# Clock_Schematic_v_4.net
KiCad netlist of a schematic drawn in EAGLE
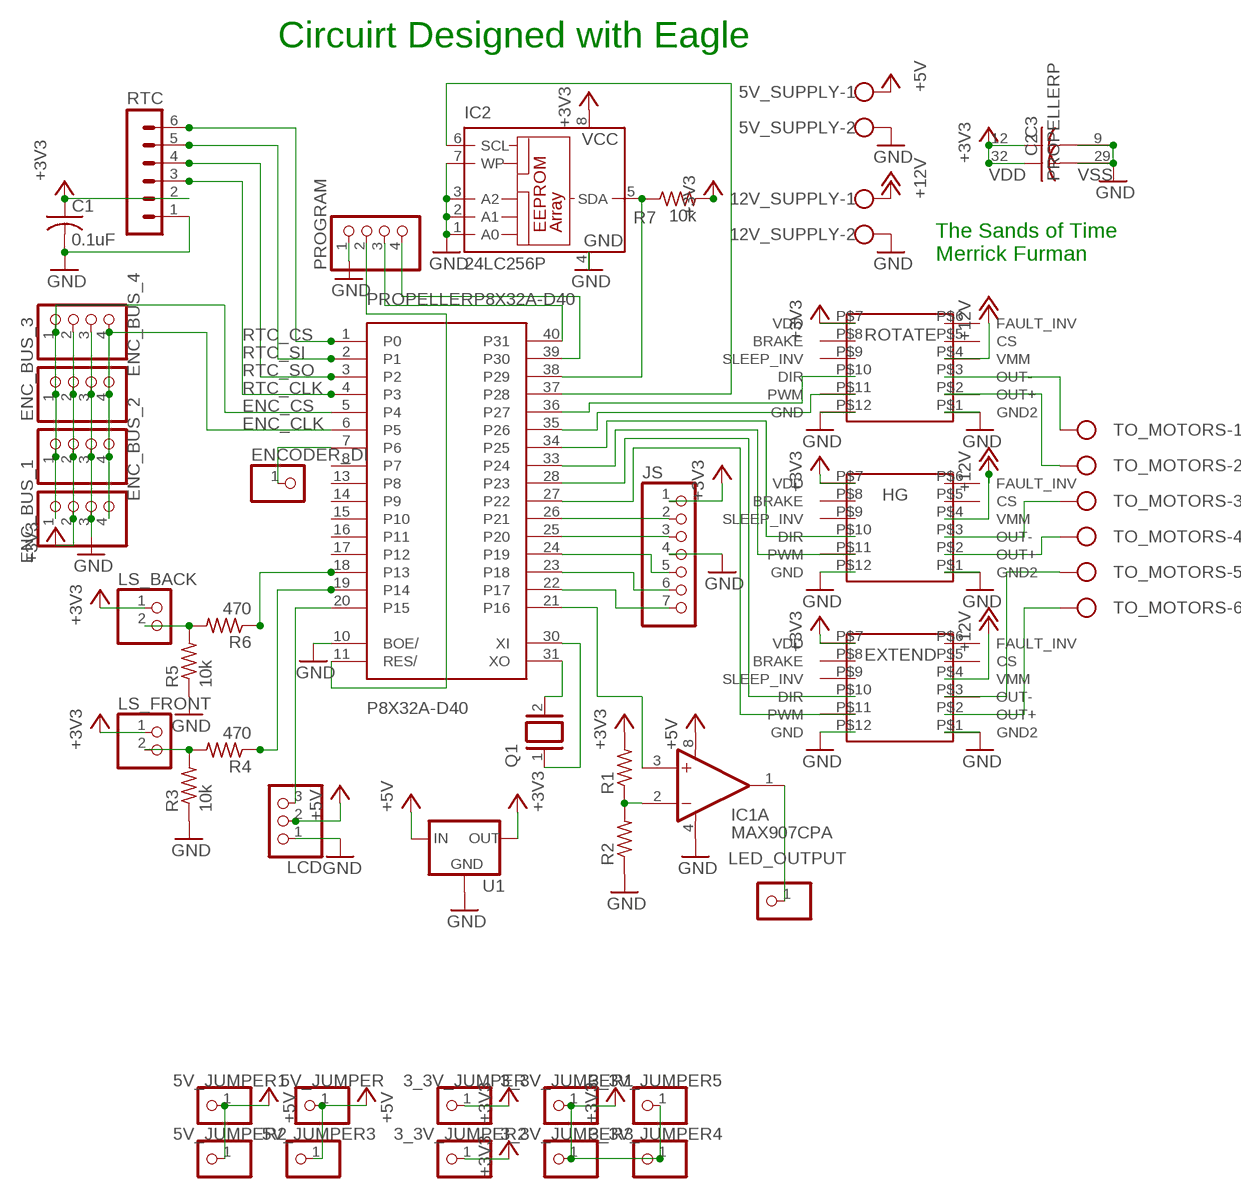
[diagram p0: schematic, sheet 1]

(export (version "E")
  (design (tool "Eeschema 10.0.6"))
  (components
    (comp (ref "3_3V_JUMPER")
      (value "PINHD-1X1")
      (footprint "eagle-import:1X01")
      (libsource (lib "eagle-import") (part "PINHD-1X1"))
    )
    (comp (ref "3_3V_JUMPER1")
      (value "PINHD-1X1")
      (footprint "eagle-import:1X01")
      (libsource (lib "eagle-import") (part "PINHD-1X1"))
    )
    (comp (ref "3_3V_JUMPER2")
      (value "PINHD-1X1")
      (footprint "eagle-import:1X01")
      (libsource (lib "eagle-import") (part "PINHD-1X1"))
    )
    (comp (ref "3_3V_JUMPER3")
      (value "PINHD-1X1")
      (footprint "eagle-import:1X01")
      (libsource (lib "eagle-import") (part "PINHD-1X1"))
    )
    (comp (ref "3_3V_JUMPER4")
      (value "PINHD-1X1")
      (footprint "eagle-import:1X01")
      (libsource (lib "eagle-import") (part "PINHD-1X1"))
    )
    (comp (ref "3_3V_JUMPER5")
      (value "PINHD-1X1")
      (footprint "eagle-import:1X01")
      (libsource (lib "eagle-import") (part "PINHD-1X1"))
    )
    (comp (ref "5V_JUMPER")
      (value "PINHD-1X1")
      (footprint "eagle-import:1X01")
      (libsource (lib "eagle-import") (part "PINHD-1X1"))
    )
    (comp (ref "5V_JUMPER1")
      (value "PINHD-1X1")
      (footprint "eagle-import:1X01")
      (libsource (lib "eagle-import") (part "PINHD-1X1"))
    )
    (comp (ref "5V_JUMPER2")
      (value "PINHD-1X1")
      (footprint "eagle-import:1X01")
      (libsource (lib "eagle-import") (part "PINHD-1X1"))
    )
    (comp (ref "5V_JUMPER3")
      (value "PINHD-1X1")
      (footprint "eagle-import:1X01")
      (libsource (lib "eagle-import") (part "PINHD-1X1"))
    )
    (comp (ref "5V_SUPPLY")
      (value "W237-102")
      (footprint "eagle-import:W237-102")
      (fields (field (name "MPN") "237-102"))
      (libsource (lib "eagle-import") (part "W237-102"))
    )
    (comp (ref "12V_SUPPLY")
      (value "W237-102")
      (footprint "eagle-import:W237-102")
      (fields (field (name "MPN") "237-102"))
      (libsource (lib "eagle-import") (part "W237-102"))
    )
    (comp (ref "C1")
      (value "0.1uF")
      (footprint "eagle-import:C050-025X075")
      (libsource (lib "eagle-import") (part "C-US050-025X075"))
    )
    (comp (ref "C2")
      (value "C-US050-025X075")
      (footprint "eagle-import:C050-025X075")
      (libsource (lib "eagle-import") (part "C-US050-025X075"))
    )
    (comp (ref "C3")
      (value "C-US050-025X075")
      (footprint "eagle-import:C050-025X075")
      (libsource (lib "eagle-import") (part "C-US050-025X075"))
    )
    (comp (ref "ENCODER_DI")
      (value "PINHD-1X1")
      (footprint "eagle-import:1X01")
      (libsource (lib "eagle-import") (part "PINHD-1X1"))
    )
    (comp (ref "ENC_BUS_1")
      (value "PINHD-1X4")
      (footprint "eagle-import:1X04")
      (libsource (lib "eagle-import") (part "PINHD-1X4"))
    )
    (comp (ref "ENC_BUS_2")
      (value "PINHD-1X4")
      (footprint "eagle-import:1X04")
      (libsource (lib "eagle-import") (part "PINHD-1X4"))
    )
    (comp (ref "ENC_BUS_3")
      (value "PINHD-1X4")
      (footprint "eagle-import:1X04")
      (libsource (lib "eagle-import") (part "PINHD-1X4"))
    )
    (comp (ref "ENC_BUS_4")
      (value "PINHD-1X4")
      (footprint "eagle-import:1X04")
      (libsource (lib "eagle-import") (part "PINHD-1X4"))
    )
    (comp (ref "EXTEND")
      (value "DRV")
      (footprint "eagle-import:DRV")
      (libsource (lib "eagle-import") (part "DRV"))
    )
    (comp (ref "HG")
      (value "DRV")
      (footprint "eagle-import:DRV")
      (libsource (lib "eagle-import") (part "DRV"))
    )
    (comp (ref "IC1")
      (value "MAX907CPA")
      (footprint "eagle-import:DIL08")
      (fields (field (name "MF") "MAXIM"))
      (libsource (lib "eagle-import") (part "MAX907CPA"))
    )
    (comp (ref "IC2")
      (value "24LC256P")
      (footprint "eagle-import:DIL8")
      (fields (field (name "MF") "MICROCHIP") (field (name "MPN") "24LC256-E/P"))
      (libsource (lib "eagle-import") (part "24PLC256"))
    )
    (comp (ref "JS")
      (value "PINHD-1X7")
      (footprint "eagle-import:1X07")
      (libsource (lib "eagle-import") (part "PINHD-1X7"))
    )
    (comp (ref "LCD")
      (value "PINHD-1X3")
      (footprint "eagle-import:1X03")
      (libsource (lib "eagle-import") (part "PINHD-1X3"))
    )
    (comp (ref "LED_OUTPUT")
      (value "PINHD-1X1")
      (footprint "eagle-import:1X01")
      (libsource (lib "eagle-import") (part "PINHD-1X1"))
    )
    (comp (ref "LS_BACK")
      (value "PINHD-1X2")
      (footprint "eagle-import:1X02")
      (libsource (lib "eagle-import") (part "PINHD-1X2"))
    )
    (comp (ref "LS_FRONT")
      (value "PINHD-1X2")
      (footprint "eagle-import:1X02")
      (libsource (lib "eagle-import") (part "PINHD-1X2"))
    )
    (comp (ref "PROGRAM")
      (value "PINHD-1X4")
      (footprint "eagle-import:1X04")
      (libsource (lib "eagle-import") (part "PINHD-1X4"))
    )
    (comp (ref "PROPELLER")
      (value "P8X32A-D40")
      (footprint "eagle-import:P8X32A-D40")
      (libsource (lib "eagle-import") (part "P8X32A-D40"))
    )
    (comp (ref "Q1")
      (value "XTAL/S")
      (footprint "eagle-import:QS")
      (libsource (lib "eagle-import") (part "XTAL/S"))
    )
    (comp (ref "R1")
      (value "R-US_0207/10")
      (footprint "eagle-import:0207_10")
      (libsource (lib "eagle-import") (part "R-US_0207/10"))
    )
    (comp (ref "R2")
      (value "R-US_0207/10")
      (footprint "eagle-import:0207_10")
      (libsource (lib "eagle-import") (part "R-US_0207/10"))
    )
    (comp (ref "R3")
      (value "10k")
      (footprint "eagle-import:0207_10")
      (libsource (lib "eagle-import") (part "R-US_0207/10"))
    )
    (comp (ref "R4")
      (value "470")
      (footprint "eagle-import:0207_10")
      (libsource (lib "eagle-import") (part "R-US_0207/10"))
    )
    (comp (ref "R5")
      (value "10k")
      (footprint "eagle-import:0207_10")
      (libsource (lib "eagle-import") (part "R-US_0207/10"))
    )
    (comp (ref "R6")
      (value "470")
      (footprint "eagle-import:0207_10")
      (libsource (lib "eagle-import") (part "R-US_0207/10"))
    )
    (comp (ref "R7")
      (value "10k")
      (footprint "eagle-import:0207_10")
      (libsource (lib "eagle-import") (part "R-US_0207/10"))
    )
    (comp (ref "ROTATE")
      (value "DRV")
      (footprint "eagle-import:DRV")
      (libsource (lib "eagle-import") (part "DRV"))
    )
    (comp (ref "RTC")
      (value "MA06-1")
      (footprint "eagle-import:MA06-1")
      (libsource (lib "eagle-import") (part "MA06-1"))
    )
    (comp (ref "TO_MOTORS")
      (value "W237-6")
      (footprint "eagle-import:W237-6")
      (libsource (lib "eagle-import") (part "W237-6"))
    )
    (comp (ref "U1")
      (value "V_REG_78XXSIDE")
      (footprint "eagle-import:78XXL")
      (libsource (lib "eagle-import") (part "V_REG_78XXSIDE"))
    )
  )
  (nets
    (net (code "1") (name "+3V3") (class "Default")
      (node (ref "3_3V_JUMPER") (pin "1") (pinfunction "1_1") (pintype "passive"))
      (node (ref "3_3V_JUMPER1") (pin "1") (pinfunction "1_1") (pintype "passive"))
      (node (ref "3_3V_JUMPER2") (pin "1") (pinfunction "1_1") (pintype "passive"))
      (node (ref "3_3V_JUMPER3") (pin "1") (pinfunction "1_1") (pintype "passive"))
      (node (ref "3_3V_JUMPER4") (pin "1") (pinfunction "1_1") (pintype "passive"))
      (node (ref "3_3V_JUMPER5") (pin "1") (pinfunction "1_1") (pintype "passive"))
      (node (ref "C1") (pin "1") (pinfunction "1_1") (pintype "passive"))
      (node (ref "C2") (pin "1") (pinfunction "1_1") (pintype "passive"))
      (node (ref "C3") (pin "1") (pinfunction "1_1") (pintype "passive"))
      (node (ref "ENC_BUS_1") (pin "2") (pinfunction "2_2") (pintype "passive"))
      (node (ref "ENC_BUS_2") (pin "2") (pinfunction "2_2") (pintype "passive"))
      (node (ref "ENC_BUS_3") (pin "2") (pinfunction "2_2") (pintype "passive"))
      (node (ref "ENC_BUS_4") (pin "2") (pinfunction "2_2") (pintype "passive"))
      (node (ref "EXTEND") (pin "P$7") (pinfunction "VDD_P$7") (pintype "bidirectional"))
      (node (ref "HG") (pin "P$7") (pinfunction "VDD_P$7") (pintype "bidirectional"))
      (node (ref "IC2") (pin "8") (pinfunction "VCC_8") (pintype "power_in"))
      (node (ref "JS") (pin "1") (pinfunction "1_1") (pintype "passive"))
      (node (ref "LS_BACK") (pin "1") (pinfunction "1_1") (pintype "passive"))
      (node (ref "LS_FRONT") (pin "1") (pinfunction "1_1") (pintype "passive"))
      (node (ref "PROPELLER") (pin "12") (pinfunction "VDD_12") (pintype "power_in"))
      (node (ref "PROPELLER") (pin "32") (pinfunction "VDD_32") (pintype "power_in"))
      (node (ref "R1") (pin "2") (pinfunction "2_2") (pintype "passive"))
      (node (ref "R7") (pin "2") (pinfunction "2_2") (pintype "passive"))
      (node (ref "ROTATE") (pin "P$7") (pinfunction "VDD_P$7") (pintype "bidirectional"))
      (node (ref "RTC") (pin "2") (pinfunction "2_2") (pintype "passive"))
      (node (ref "U1") (pin "OUT") (pinfunction "OUT_OUT") (pintype "passive"))
    )
    (net (code "2") (name "+5V") (class "Default")
      (node (ref "5V_JUMPER") (pin "1") (pinfunction "1_1") (pintype "passive"))
      (node (ref "5V_JUMPER1") (pin "1") (pinfunction "1_1") (pintype "passive"))
      (node (ref "5V_JUMPER2") (pin "1") (pinfunction "1_1") (pintype "passive"))
      (node (ref "5V_JUMPER3") (pin "1") (pinfunction "1_1") (pintype "passive"))
      (node (ref "5V_SUPPLY") (pin "1") (pinfunction "KL_1") (pintype "passive"))
      (node (ref "IC1") (pin "8") (pinfunction "V+_8") (pintype "power_in"))
      (node (ref "LCD") (pin "2") (pinfunction "2_2") (pintype "passive"))
      (node (ref "U1") (pin "IN") (pinfunction "IN_IN") (pintype "input"))
    )
    (net (code "3") (name "+12V") (class "Default")
      (node (ref "12V_SUPPLY") (pin "1") (pinfunction "KL_1") (pintype "passive"))
      (node (ref "EXTEND") (pin "P$4") (pinfunction "VMM_P$4") (pintype "bidirectional"))
      (node (ref "HG") (pin "P$4") (pinfunction "VMM_P$4") (pintype "bidirectional"))
      (node (ref "ROTATE") (pin "P$4") (pinfunction "VMM_P$4") (pintype "bidirectional"))
    )
    (net (code "4") (name "/ENC_CLK") (class "Default")
      (node (ref "ENC_BUS_1") (pin "4") (pinfunction "4_4") (pintype "passive"))
      (node (ref "ENC_BUS_2") (pin "4") (pinfunction "4_4") (pintype "passive"))
      (node (ref "ENC_BUS_3") (pin "4") (pinfunction "4_4") (pintype "passive"))
      (node (ref "ENC_BUS_4") (pin "4") (pinfunction "4_4") (pintype "passive"))
      (node (ref "PROPELLER") (pin "6") (pinfunction "P5_6") (pintype "bidirectional"))
    )
    (net (code "5") (name "/ENC_CS") (class "Default")
      (node (ref "ENC_BUS_1") (pin "1") (pinfunction "1_1") (pintype "passive"))
      (node (ref "ENC_BUS_2") (pin "1") (pinfunction "1_1") (pintype "passive"))
      (node (ref "ENC_BUS_3") (pin "1") (pinfunction "1_1") (pintype "passive"))
      (node (ref "ENC_BUS_4") (pin "1") (pinfunction "1_1") (pintype "passive"))
      (node (ref "PROPELLER") (pin "5") (pinfunction "P4_5") (pintype "bidirectional"))
    )
    (net (code "6") (name "/RTC_CLK") (class "Default")
      (node (ref "PROPELLER") (pin "4") (pinfunction "P3_4") (pintype "bidirectional"))
      (node (ref "RTC") (pin "3") (pinfunction "3_3") (pintype "passive"))
    )
    (net (code "7") (name "/RTC_CS") (class "Default")
      (node (ref "PROPELLER") (pin "1") (pinfunction "P0_1") (pintype "bidirectional"))
      (node (ref "RTC") (pin "6") (pinfunction "6_6") (pintype "passive"))
    )
    (net (code "8") (name "/RTC_SI") (class "Default")
      (node (ref "PROPELLER") (pin "2") (pinfunction "P1_2") (pintype "bidirectional"))
      (node (ref "RTC") (pin "5") (pinfunction "5_5") (pintype "passive"))
    )
    (net (code "9") (name "/RTC_SO") (class "Default")
      (node (ref "PROPELLER") (pin "3") (pinfunction "P2_3") (pintype "bidirectional"))
      (node (ref "RTC") (pin "4") (pinfunction "4_4") (pintype "passive"))
    )
    (net (code "10") (name "GND") (class "Default")
      (node (ref "12V_SUPPLY") (pin "2") (pinfunction "KL_2") (pintype "passive"))
      (node (ref "5V_SUPPLY") (pin "2") (pinfunction "KL_2") (pintype "passive"))
      (node (ref "C1") (pin "2") (pinfunction "2_2") (pintype "passive"))
      (node (ref "C2") (pin "2") (pinfunction "2_2") (pintype "passive"))
      (node (ref "C3") (pin "2") (pinfunction "2_2") (pintype "passive"))
      (node (ref "ENC_BUS_1") (pin "3") (pinfunction "3_3") (pintype "passive"))
      (node (ref "ENC_BUS_2") (pin "3") (pinfunction "3_3") (pintype "passive"))
      (node (ref "ENC_BUS_3") (pin "3") (pinfunction "3_3") (pintype "passive"))
      (node (ref "ENC_BUS_4") (pin "3") (pinfunction "3_3") (pintype "passive"))
      (node (ref "EXTEND") (pin "P$1") (pinfunction "GND2_P$1") (pintype "bidirectional"))
      (node (ref "EXTEND") (pin "P$12") (pinfunction "GND_P$12") (pintype "bidirectional"))
      (node (ref "HG") (pin "P$1") (pinfunction "GND2_P$1") (pintype "bidirectional"))
      (node (ref "HG") (pin "P$12") (pinfunction "GND_P$12") (pintype "bidirectional"))
      (node (ref "IC1") (pin "4") (pinfunction "V-_4") (pintype "power_in"))
      (node (ref "IC2") (pin "1") (pinfunction "A0_1") (pintype "input"))
      (node (ref "IC2") (pin "2") (pinfunction "A1_2") (pintype "input"))
      (node (ref "IC2") (pin "3") (pinfunction "A2_3") (pintype "input"))
      (node (ref "IC2") (pin "4") (pinfunction "GND_4") (pintype "power_in"))
      (node (ref "IC2") (pin "7") (pinfunction "WP_7") (pintype "input"))
      (node (ref "JS") (pin "4") (pinfunction "4_4") (pintype "passive"))
      (node (ref "LCD") (pin "1") (pinfunction "1_1") (pintype "passive"))
      (node (ref "PROGRAM") (pin "1") (pinfunction "1_1") (pintype "passive"))
      (node (ref "PROPELLER") (pin "10") (pinfunction "BOE/_10") (pintype "input"))
      (node (ref "PROPELLER") (pin "29") (pinfunction "VSS_29") (pintype "power_in"))
      (node (ref "PROPELLER") (pin "9") (pinfunction "VSS_9") (pintype "power_in"))
      (node (ref "R2") (pin "1") (pinfunction "1_1") (pintype "passive"))
      (node (ref "R3") (pin "1") (pinfunction "1_1") (pintype "passive"))
      (node (ref "R5") (pin "1") (pinfunction "1_1") (pintype "passive"))
      (node (ref "ROTATE") (pin "P$1") (pinfunction "GND2_P$1") (pintype "bidirectional"))
      (node (ref "ROTATE") (pin "P$12") (pinfunction "GND_P$12") (pintype "bidirectional"))
      (node (ref "RTC") (pin "1") (pinfunction "1_1") (pintype "passive"))
      (node (ref "U1") (pin "GND") (pinfunction "GND_GND") (pintype "input"))
    )
    (net (code "11") (name "Net-(EXTEND-DIR)") (class "Default")
      (node (ref "EXTEND") (pin "P$10") (pinfunction "DIR_P$10") (pintype "bidirectional"))
      (node (ref "PROPELLER") (pin "28") (pinfunction "P23_28") (pintype "bidirectional"))
    )
    (net (code "12") (name "Net-(EXTEND-OUT+)") (class "Default")
      (node (ref "EXTEND") (pin "P$2") (pinfunction "OUT+_P$2") (pintype "bidirectional"))
      (node (ref "TO_MOTORS") (pin "6") (pinfunction "KL_6") (pintype "passive"))
    )
    (net (code "13") (name "Net-(EXTEND-OUT-)") (class "Default")
      (node (ref "EXTEND") (pin "P$3") (pinfunction "OUT-_P$3") (pintype "bidirectional"))
      (node (ref "TO_MOTORS") (pin "5") (pinfunction "KL_5") (pintype "passive"))
    )
    (net (code "14") (name "Net-(EXTEND-PWM)") (class "Default")
      (node (ref "EXTEND") (pin "P$11") (pinfunction "PWM_P$11") (pintype "bidirectional"))
      (node (ref "PROPELLER") (pin "27") (pinfunction "P22_27") (pintype "bidirectional"))
    )
    (net (code "15") (name "Net-(HG-DIR)") (class "Default")
      (node (ref "HG") (pin "P$10") (pinfunction "DIR_P$10") (pintype "bidirectional"))
      (node (ref "PROPELLER") (pin "34") (pinfunction "P25_34") (pintype "bidirectional"))
    )
    (net (code "16") (name "Net-(HG-OUT+)") (class "Default")
      (node (ref "HG") (pin "P$2") (pinfunction "OUT+_P$2") (pintype "bidirectional"))
      (node (ref "TO_MOTORS") (pin "4") (pinfunction "KL_4") (pintype "passive"))
    )
    (net (code "17") (name "Net-(HG-OUT-)") (class "Default")
      (node (ref "HG") (pin "P$3") (pinfunction "OUT-_P$3") (pintype "bidirectional"))
      (node (ref "TO_MOTORS") (pin "3") (pinfunction "KL_3") (pintype "passive"))
    )
    (net (code "18") (name "Net-(HG-PWM)") (class "Default")
      (node (ref "HG") (pin "P$11") (pinfunction "PWM_P$11") (pintype "bidirectional"))
      (node (ref "PROPELLER") (pin "33") (pinfunction "P24_33") (pintype "bidirectional"))
    )
    (net (code "19") (name "Net-(IC1A-+IN)") (class "Default")
      (node (ref "IC1") (pin "3") (pinfunction "+IN_3") (pintype "input"))
      (node (ref "PROPELLER") (pin "21") (pinfunction "P16_21") (pintype "bidirectional"))
    )
    (net (code "20") (name "Net-(IC1A--IN)") (class "Default")
      (node (ref "IC1") (pin "2") (pinfunction "-IN_2") (pintype "input"))
      (node (ref "R1") (pin "1") (pinfunction "1_1") (pintype "passive"))
      (node (ref "R2") (pin "2") (pinfunction "2_2") (pintype "passive"))
    )
    (net (code "21") (name "Net-(IC1A-OUT)") (class "Default")
      (node (ref "IC1") (pin "1") (pinfunction "OUT_1") (pintype "output"))
      (node (ref "LED_OUTPUT") (pin "1") (pinfunction "1_1") (pintype "passive"))
    )
    (net (code "22") (name "Net-(IC2-SCL)") (class "Default")
      (node (ref "IC2") (pin "6") (pinfunction "SCL_6") (pintype "input"))
      (node (ref "PROPELLER") (pin "37") (pinfunction "P28_37") (pintype "bidirectional"))
    )
    (net (code "23") (name "Net-(IC2-SDA)") (class "Default")
      (node (ref "IC2") (pin "5") (pinfunction "SDA_5") (pintype "bidirectional"))
      (node (ref "PROPELLER") (pin "38") (pinfunction "P29_38") (pintype "bidirectional"))
      (node (ref "R7") (pin "1") (pinfunction "1_1") (pintype "passive"))
    )
    (net (code "24") (name "Net-(LS_BACK-Pad2)") (class "Default")
      (node (ref "LS_BACK") (pin "2") (pinfunction "2_2") (pintype "passive"))
      (node (ref "R5") (pin "2") (pinfunction "2_2") (pintype "passive"))
      (node (ref "R6") (pin "2") (pinfunction "2_2") (pintype "passive"))
    )
    (net (code "25") (name "Net-(LS_FRONT-Pad2)") (class "Default")
      (node (ref "LS_FRONT") (pin "2") (pinfunction "2_2") (pintype "passive"))
      (node (ref "R3") (pin "2") (pinfunction "2_2") (pintype "passive"))
      (node (ref "R4") (pin "2") (pinfunction "2_2") (pintype "passive"))
    )
    (net (code "26") (name "Net-(PROPELLERB-P6)") (class "Default")
      (node (ref "ENCODER_DI") (pin "1") (pinfunction "1_1") (pintype "passive"))
      (node (ref "PROPELLER") (pin "7") (pinfunction "P6_7") (pintype "bidirectional"))
    )
    (net (code "27") (name "Net-(PROPELLERB-P13)") (class "Default")
      (node (ref "PROPELLER") (pin "18") (pinfunction "P13_18") (pintype "bidirectional"))
      (node (ref "R6") (pin "1") (pinfunction "1_1") (pintype "passive"))
    )
    (net (code "28") (name "Net-(PROPELLERB-P14)") (class "Default")
      (node (ref "PROPELLER") (pin "19") (pinfunction "P14_19") (pintype "bidirectional"))
      (node (ref "R4") (pin "1") (pinfunction "1_1") (pintype "passive"))
    )
    (net (code "29") (name "Net-(PROPELLERB-P15)") (class "Default")
      (node (ref "LCD") (pin "3") (pinfunction "3_3") (pintype "passive"))
      (node (ref "PROPELLER") (pin "20") (pinfunction "P15_20") (pintype "bidirectional"))
    )
    (net (code "30") (name "Net-(PROPELLERB-P17)") (class "Default")
      (node (ref "JS") (pin "7") (pinfunction "7_7") (pintype "passive"))
      (node (ref "PROPELLER") (pin "22") (pinfunction "P17_22") (pintype "bidirectional"))
    )
    (net (code "31") (name "Net-(PROPELLERB-P18)") (class "Default")
      (node (ref "JS") (pin "6") (pinfunction "6_6") (pintype "passive"))
      (node (ref "PROPELLER") (pin "23") (pinfunction "P18_23") (pintype "bidirectional"))
    )
    (net (code "32") (name "Net-(PROPELLERB-P19)") (class "Default")
      (node (ref "JS") (pin "5") (pinfunction "5_5") (pintype "passive"))
      (node (ref "PROPELLER") (pin "24") (pinfunction "P19_24") (pintype "bidirectional"))
    )
    (net (code "33") (name "Net-(PROPELLERB-P20)") (class "Default")
      (node (ref "JS") (pin "3") (pinfunction "3_3") (pintype "passive"))
      (node (ref "PROPELLER") (pin "25") (pinfunction "P20_25") (pintype "bidirectional"))
    )
    (net (code "34") (name "Net-(PROPELLERB-P21)") (class "Default")
      (node (ref "JS") (pin "2") (pinfunction "2_2") (pintype "passive"))
      (node (ref "PROPELLER") (pin "26") (pinfunction "P21_26") (pintype "bidirectional"))
    )
    (net (code "35") (name "Net-(PROPELLERB-P26)") (class "Default")
      (node (ref "PROPELLER") (pin "35") (pinfunction "P26_35") (pintype "bidirectional"))
      (node (ref "ROTATE") (pin "P$11") (pinfunction "PWM_P$11") (pintype "bidirectional"))
    )
    (net (code "36") (name "Net-(PROPELLERB-P27)") (class "Default")
      (node (ref "PROPELLER") (pin "36") (pinfunction "P27_36") (pintype "bidirectional"))
      (node (ref "ROTATE") (pin "P$10") (pinfunction "DIR_P$10") (pintype "bidirectional"))
    )
    (net (code "37") (name "Net-(PROPELLERB-P30)") (class "Default")
      (node (ref "PROGRAM") (pin "4") (pinfunction "4_4") (pintype "passive"))
      (node (ref "PROPELLER") (pin "39") (pinfunction "P30_39") (pintype "bidirectional"))
    )
    (net (code "38") (name "Net-(PROPELLERB-P31)") (class "Default")
      (node (ref "PROGRAM") (pin "3") (pinfunction "3_3") (pintype "passive"))
      (node (ref "PROPELLER") (pin "40") (pinfunction "P31_40") (pintype "bidirectional"))
    )
    (net (code "39") (name "Net-(PROPELLERB-RES{slash})") (class "Default")
      (node (ref "PROGRAM") (pin "2") (pinfunction "2_2") (pintype "passive"))
      (node (ref "PROPELLER") (pin "11") (pinfunction "RES/_11") (pintype "bidirectional"))
    )
    (net (code "40") (name "Net-(PROPELLERB-XI)") (class "Default")
      (node (ref "PROPELLER") (pin "30") (pinfunction "XI_30") (pintype "input"))
      (node (ref "Q1") (pin "1") (pinfunction "1_1") (pintype "passive"))
    )
    (net (code "41") (name "Net-(PROPELLERB-XO)") (class "Default")
      (node (ref "PROPELLER") (pin "31") (pinfunction "XO_31") (pintype "output"))
      (node (ref "Q1") (pin "2") (pinfunction "2_2") (pintype "passive"))
    )
    (net (code "42") (name "Net-(ROTATE-OUT+)") (class "Default")
      (node (ref "ROTATE") (pin "P$2") (pinfunction "OUT+_P$2") (pintype "bidirectional"))
      (node (ref "TO_MOTORS") (pin "2") (pinfunction "KL_2") (pintype "passive"))
    )
    (net (code "43") (name "Net-(ROTATE-OUT-)") (class "Default")
      (node (ref "ROTATE") (pin "P$3") (pinfunction "OUT-_P$3") (pintype "bidirectional"))
      (node (ref "TO_MOTORS") (pin "1") (pinfunction "KL_1") (pintype "passive"))
    )
    (net (code "44") (name "unconnected-(EXTEND-BRAKE-PadP$8)") (class "Default")
      (node (ref "EXTEND") (pin "P$8") (pinfunction "BRAKE_P$8") (pintype "bidirectional"))
    )
    (net (code "45") (name "unconnected-(EXTEND-CS-PadP$5)") (class "Default")
      (node (ref "EXTEND") (pin "P$5") (pinfunction "CS_P$5") (pintype "bidirectional"))
    )
    (net (code "46") (name "unconnected-(EXTEND-FAULT_INV-PadP$6)") (class "Default")
      (node (ref "EXTEND") (pin "P$6") (pinfunction "FAULT_INV_P$6") (pintype "bidirectional"))
    )
    (net (code "47") (name "unconnected-(EXTEND-SLEEP_INV-PadP$9)") (class "Default")
      (node (ref "EXTEND") (pin "P$9") (pinfunction "SLEEP_INV_P$9") (pintype "bidirectional"))
    )
    (net (code "48") (name "unconnected-(HG-BRAKE-PadP$8)") (class "Default")
      (node (ref "HG") (pin "P$8") (pinfunction "BRAKE_P$8") (pintype "bidirectional"))
    )
    (net (code "49") (name "unconnected-(HG-CS-PadP$5)") (class "Default")
      (node (ref "HG") (pin "P$5") (pinfunction "CS_P$5") (pintype "bidirectional"))
    )
    (net (code "50") (name "unconnected-(HG-FAULT_INV-PadP$6)") (class "Default")
      (node (ref "HG") (pin "P$6") (pinfunction "FAULT_INV_P$6") (pintype "bidirectional"))
    )
    (net (code "51") (name "unconnected-(HG-SLEEP_INV-PadP$9)") (class "Default")
      (node (ref "HG") (pin "P$9") (pinfunction "SLEEP_INV_P$9") (pintype "bidirectional"))
    )
    (net (code "52") (name "unconnected-(PROPELLERB-P7-Pad8)") (class "Default")
      (node (ref "PROPELLER") (pin "8") (pinfunction "P7_8") (pintype "bidirectional"))
    )
    (net (code "53") (name "unconnected-(PROPELLERB-P8-Pad13)") (class "Default")
      (node (ref "PROPELLER") (pin "13") (pinfunction "P8_13") (pintype "bidirectional"))
    )
    (net (code "54") (name "unconnected-(PROPELLERB-P9-Pad14)") (class "Default")
      (node (ref "PROPELLER") (pin "14") (pinfunction "P9_14") (pintype "bidirectional"))
    )
    (net (code "55") (name "unconnected-(PROPELLERB-P10-Pad15)") (class "Default")
      (node (ref "PROPELLER") (pin "15") (pinfunction "P10_15") (pintype "bidirectional"))
    )
    (net (code "56") (name "unconnected-(PROPELLERB-P11-Pad16)") (class "Default")
      (node (ref "PROPELLER") (pin "16") (pinfunction "P11_16") (pintype "bidirectional"))
    )
    (net (code "57") (name "unconnected-(PROPELLERB-P12-Pad17)") (class "Default")
      (node (ref "PROPELLER") (pin "17") (pinfunction "P12_17") (pintype "bidirectional"))
    )
    (net (code "58") (name "unconnected-(ROTATE-BRAKE-PadP$8)") (class "Default")
      (node (ref "ROTATE") (pin "P$8") (pinfunction "BRAKE_P$8") (pintype "bidirectional"))
    )
    (net (code "59") (name "unconnected-(ROTATE-CS-PadP$5)") (class "Default")
      (node (ref "ROTATE") (pin "P$5") (pinfunction "CS_P$5") (pintype "bidirectional"))
    )
    (net (code "60") (name "unconnected-(ROTATE-FAULT_INV-PadP$6)") (class "Default")
      (node (ref "ROTATE") (pin "P$6") (pinfunction "FAULT_INV_P$6") (pintype "bidirectional"))
    )
    (net (code "61") (name "unconnected-(ROTATE-SLEEP_INV-PadP$9)") (class "Default")
      (node (ref "ROTATE") (pin "P$9") (pinfunction "SLEEP_INV_P$9") (pintype "bidirectional"))
    )
  )
)
